# Int_Termostat.net
KiCad netlist of a schematic drawn in EAGLE
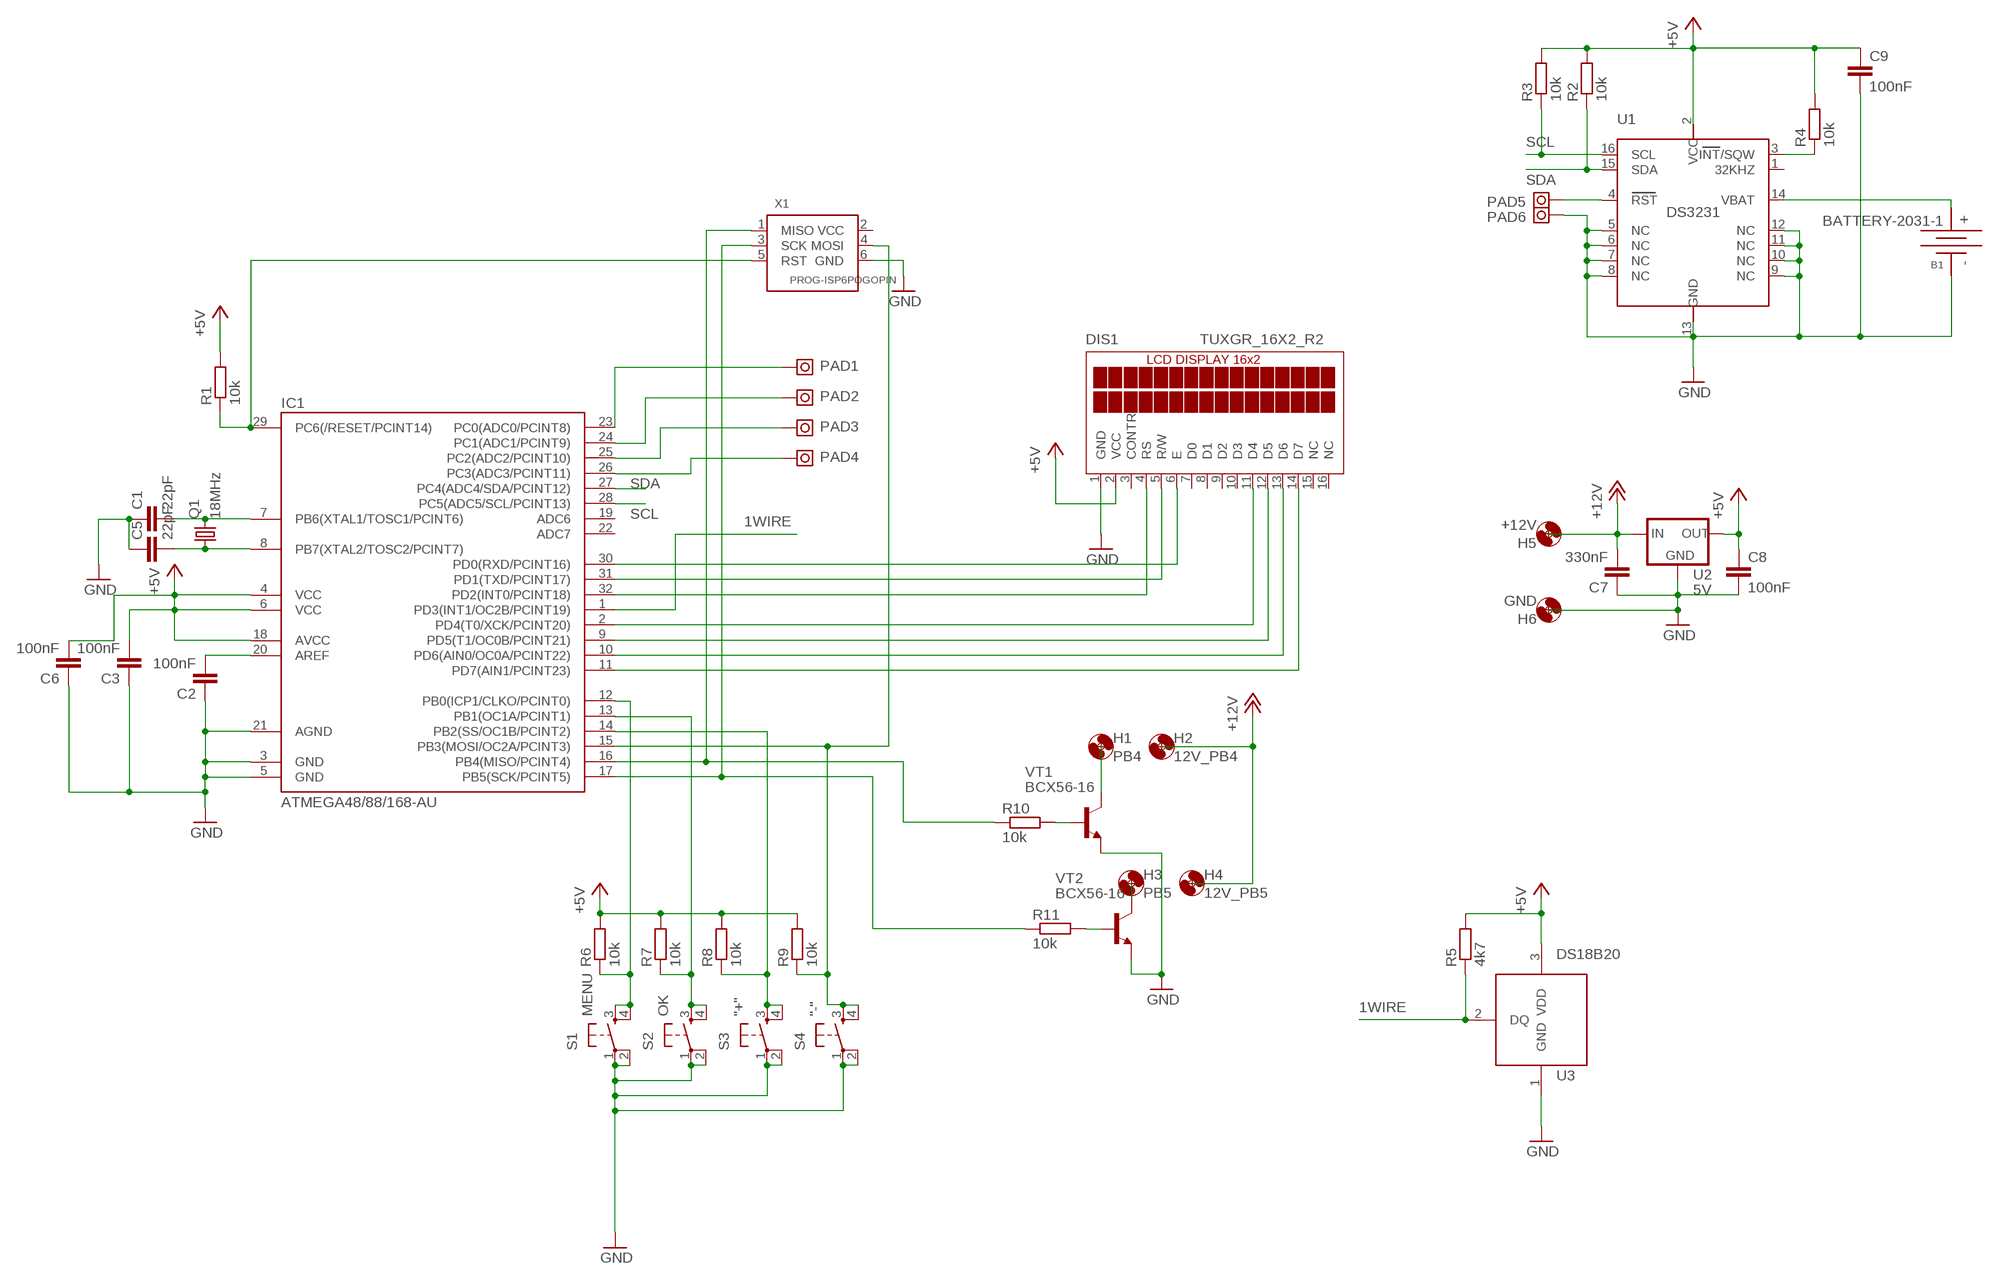
[diagram p0: schematic, sheet 1]

(export (version "E")
  (design (tool "Eeschema 10.0.6"))
  (components
    (comp (ref "B1")
      (value "BATTERY-2031-1")
      (footprint "eagle-import:BTH2032-1")
      (libsource (lib "eagle-import") (part "BATTERY-2031-1"))
    )
    (comp (ref "C1")
      (value "22pF")
      (footprint "eagle-import:C0805")
      (libsource (lib "eagle-import") (part "C-EUC0805"))
    )
    (comp (ref "C2")
      (value "100nF")
      (footprint "eagle-import:C0805")
      (libsource (lib "eagle-import") (part "C-EUC0805"))
    )
    (comp (ref "C3")
      (value "100nF")
      (footprint "eagle-import:C0805")
      (libsource (lib "eagle-import") (part "C-EUC0805"))
    )
    (comp (ref "C5")
      (value "22pF")
      (footprint "eagle-import:C0805")
      (libsource (lib "eagle-import") (part "C-EUC0805"))
    )
    (comp (ref "C6")
      (value "100nF")
      (footprint "eagle-import:C0805")
      (libsource (lib "eagle-import") (part "C-EUC0805"))
    )
    (comp (ref "C7")
      (value "330nF")
      (footprint "eagle-import:C0805")
      (libsource (lib "eagle-import") (part "C-EUC0805"))
    )
    (comp (ref "C8")
      (value "100nF")
      (footprint "eagle-import:C0805")
      (libsource (lib "eagle-import") (part "C-EUC0805"))
    )
    (comp (ref "C9")
      (value "100nF")
      (footprint "eagle-import:C0805")
      (libsource (lib "eagle-import") (part "C-EUC0805"))
    )
    (comp (ref "DIS1")
      (value "TUXGR_16X2_R2")
      (footprint "eagle-import:TUXGR_16X2_R2")
      (libsource (lib "eagle-import") (part "TUXGR_16X2_R2"))
    )
    (comp (ref "H1")
      (value "PB4")
      (footprint "eagle-import:3,0")
      (libsource (lib "eagle-import") (part "MOUNT-HOLE3.0"))
    )
    (comp (ref "H2")
      (value "12V_PB4")
      (footprint "eagle-import:3,0")
      (libsource (lib "eagle-import") (part "MOUNT-HOLE3.0"))
    )
    (comp (ref "H3")
      (value "PB5")
      (footprint "eagle-import:3,0")
      (libsource (lib "eagle-import") (part "MOUNT-HOLE3.0"))
    )
    (comp (ref "H4")
      (value "12V_PB5")
      (footprint "eagle-import:3,0")
      (libsource (lib "eagle-import") (part "MOUNT-HOLE3.0"))
    )
    (comp (ref "H5")
      (value "+12V")
      (footprint "eagle-import:3,0")
      (libsource (lib "eagle-import") (part "MOUNT-HOLE3.0"))
    )
    (comp (ref "H6")
      (value "GND")
      (footprint "eagle-import:3,0")
      (libsource (lib "eagle-import") (part "MOUNT-HOLE3.0"))
    )
    (comp (ref "IC1")
      (value "ATMEGA48/88/168-AU")
      (footprint "eagle-import:TQFP32-08")
      (libsource (lib "eagle-import") (part "ATMEGA48/88/168-AU"))
    )
    (comp (ref "PAD1")
      (value "PC0")
      (footprint "eagle-import:PAD")
      (libsource (lib "eagle-import") (part "PAD"))
    )
    (comp (ref "PAD2")
      (value "PC1")
      (footprint "eagle-import:PAD")
      (libsource (lib "eagle-import") (part "PAD"))
    )
    (comp (ref "PAD3")
      (value "PC2")
      (footprint "eagle-import:PAD")
      (libsource (lib "eagle-import") (part "PAD"))
    )
    (comp (ref "PAD4")
      (value "PC3")
      (footprint "eagle-import:PAD")
      (libsource (lib "eagle-import") (part "PAD"))
    )
    (comp (ref "PAD5")
      (value "RST")
      (footprint "eagle-import:PAD")
      (libsource (lib "eagle-import") (part "PAD"))
    )
    (comp (ref "PAD6")
      (value "RST")
      (footprint "eagle-import:PAD")
      (libsource (lib "eagle-import") (part "PAD"))
    )
    (comp (ref "Q1")
      (value "18MHz")
      (footprint "eagle-import:HC49_S")
      (libsource (lib "eagle-import") (part "CRYSTALHC49S"))
    )
    (comp (ref "R1")
      (value "10k")
      (footprint "eagle-import:R0603")
      (libsource (lib "eagle-import") (part "R-EU_R0603"))
    )
    (comp (ref "R2")
      (value "10k")
      (footprint "eagle-import:R0603")
      (libsource (lib "eagle-import") (part "R-EU_R0603"))
    )
    (comp (ref "R3")
      (value "10k")
      (footprint "eagle-import:R0603")
      (libsource (lib "eagle-import") (part "R-EU_R0603"))
    )
    (comp (ref "R4")
      (value "10k")
      (footprint "eagle-import:R0603")
      (libsource (lib "eagle-import") (part "R-EU_R0603"))
    )
    (comp (ref "R5")
      (value "4k7")
      (footprint "eagle-import:R0603")
      (libsource (lib "eagle-import") (part "R-EU_R0603"))
    )
    (comp (ref "R6")
      (value "10k")
      (footprint "eagle-import:R0603")
      (libsource (lib "eagle-import") (part "R-EU_R0603"))
    )
    (comp (ref "R7")
      (value "10k")
      (footprint "eagle-import:R0603")
      (libsource (lib "eagle-import") (part "R-EU_R0603"))
    )
    (comp (ref "R8")
      (value "10k")
      (footprint "eagle-import:R0603")
      (libsource (lib "eagle-import") (part "R-EU_R0603"))
    )
    (comp (ref "R9")
      (value "10k")
      (footprint "eagle-import:R0603")
      (libsource (lib "eagle-import") (part "R-EU_R0603"))
    )
    (comp (ref "R10")
      (value "10k")
      (footprint "eagle-import:R0603")
      (libsource (lib "eagle-import") (part "R-EU_R0603"))
    )
    (comp (ref "R11")
      (value "10k")
      (footprint "eagle-import:R0603")
      (libsource (lib "eagle-import") (part "R-EU_R0603"))
    )
    (comp (ref "S1")
      (value "MENU")
      (footprint "eagle-import:DTS-6")
      (libsource (lib "eagle-import") (part "DTS-6"))
    )
    (comp (ref "S2")
      (value "OK")
      (footprint "eagle-import:DTS-6")
      (libsource (lib "eagle-import") (part "DTS-6"))
    )
    (comp (ref "S3")
      (value "\"+\"")
      (footprint "eagle-import:DTS-6")
      (libsource (lib "eagle-import") (part "DTS-6"))
    )
    (comp (ref "S4")
      (value "\"-\"")
      (footprint "eagle-import:DTS-6")
      (libsource (lib "eagle-import") (part "DTS-6"))
    )
    (comp (ref "U1")
      (value "DS3231")
      (footprint "eagle-import:SO16")
      (libsource (lib "eagle-import") (part "DS3231"))
    )
    (comp (ref "U2")
      (value "5V")
      (footprint "eagle-import:TO263")
      (libsource (lib "eagle-import") (part "L78XX/TO263"))
    )
    (comp (ref "U3")
      (value "DS18B20")
      (footprint "eagle-import:TO92")
      (libsource (lib "eagle-import") (part "DS18B20"))
    )
    (comp (ref "VT1")
      (value "BCX56-16")
      (footprint "eagle-import:SOT89-ECB")
      (libsource (lib "eagle-import") (part "BCX56-16"))
    )
    (comp (ref "VT2")
      (value "BCX56-16")
      (footprint "eagle-import:SOT89-ECB")
      (libsource (lib "eagle-import") (part "BCX56-16"))
    )
    (comp (ref "X1")
      (value "PROG-ISP6POGOPIN")
      (footprint "eagle-import:PROG_POGOPIN")
      (libsource (lib "eagle-import") (part "PROG-ISP6POGOPIN"))
    )
  )
  (nets
    (net (code "1") (name "+5V") (class "Default")
      (node (ref "C3") (pin "2") (pinfunction "2_2") (pintype "passive"))
      (node (ref "C6") (pin "2") (pinfunction "2_2") (pintype "passive"))
      (node (ref "C8") (pin "1") (pinfunction "1_1") (pintype "passive"))
      (node (ref "C9") (pin "1") (pinfunction "1_1") (pintype "passive"))
      (node (ref "DIS1") (pin "2") (pinfunction "VCC_2") (pintype "power_in"))
      (node (ref "IC1") (pin "18") (pinfunction "AVCC_18") (pintype "passive"))
      (node (ref "IC1") (pin "4") (pinfunction "VCC_4") (pintype "power_in"))
      (node (ref "IC1") (pin "6") (pinfunction "VCC_6") (pintype "power_in"))
      (node (ref "R1") (pin "2") (pinfunction "2_2") (pintype "passive"))
      (node (ref "R2") (pin "2") (pinfunction "2_2") (pintype "passive"))
      (node (ref "R3") (pin "2") (pinfunction "2_2") (pintype "passive"))
      (node (ref "R4") (pin "2") (pinfunction "2_2") (pintype "passive"))
      (node (ref "R5") (pin "2") (pinfunction "2_2") (pintype "passive"))
      (node (ref "R6") (pin "2") (pinfunction "2_2") (pintype "passive"))
      (node (ref "R7") (pin "2") (pinfunction "2_2") (pintype "passive"))
      (node (ref "R8") (pin "2") (pinfunction "2_2") (pintype "passive"))
      (node (ref "R9") (pin "2") (pinfunction "2_2") (pintype "passive"))
      (node (ref "U1") (pin "2") (pinfunction "VCC_2") (pintype "bidirectional"))
      (node (ref "U2") (pin "2") (pinfunction "OUT_2") (pintype "passive"))
      (node (ref "U3") (pin "3") (pinfunction "VDD_3") (pintype "power_in"))
    )
    (net (code "2") (name "+12V") (class "Default")
      (node (ref "C7") (pin "2") (pinfunction "2_2") (pintype "passive"))
      (node (ref "H2") (pin "P$1") (pinfunction "P$1_P$1") (pintype "bidirectional"))
      (node (ref "H4") (pin "P$1") (pinfunction "P$1_P$1") (pintype "bidirectional"))
      (node (ref "H5") (pin "P$1") (pinfunction "P$1_P$1") (pintype "bidirectional"))
      (node (ref "U2") (pin "1") (pinfunction "IN_1") (pintype "input"))
    )
    (net (code "3") (name "/1WIRE") (class "Default")
      (node (ref "IC1") (pin "1") (pinfunction "PD3(INT1/OC2B/PCINT19)_1") (pintype "bidirectional"))
      (node (ref "R5") (pin "1") (pinfunction "1_1") (pintype "passive"))
      (node (ref "U3") (pin "2") (pinfunction "DQ_2") (pintype "bidirectional"))
    )
    (net (code "4") (name "/SCL") (class "Default")
      (node (ref "IC1") (pin "28") (pinfunction "PC5(ADC5/SCL/PCINT13)_28") (pintype "bidirectional"))
      (node (ref "R3") (pin "1") (pinfunction "1_1") (pintype "passive"))
      (node (ref "U1") (pin "16") (pinfunction "SCL_16") (pintype "bidirectional"))
    )
    (net (code "5") (name "/SDA") (class "Default")
      (node (ref "IC1") (pin "27") (pinfunction "PC4(ADC4/SDA/PCINT12)_27") (pintype "bidirectional"))
      (node (ref "R2") (pin "1") (pinfunction "1_1") (pintype "passive"))
      (node (ref "U1") (pin "15") (pinfunction "SDA_15") (pintype "bidirectional"))
    )
    (net (code "6") (name "GND") (class "Default")
      (node (ref "B1") (pin "-") (pinfunction "-_-") (pintype "power_in"))
      (node (ref "C1") (pin "1") (pinfunction "1_1") (pintype "passive"))
      (node (ref "C2") (pin "1") (pinfunction "1_1") (pintype "passive"))
      (node (ref "C3") (pin "1") (pinfunction "1_1") (pintype "passive"))
      (node (ref "C5") (pin "1") (pinfunction "1_1") (pintype "passive"))
      (node (ref "C6") (pin "1") (pinfunction "1_1") (pintype "passive"))
      (node (ref "C7") (pin "1") (pinfunction "1_1") (pintype "passive"))
      (node (ref "C8") (pin "2") (pinfunction "2_2") (pintype "passive"))
      (node (ref "C9") (pin "2") (pinfunction "2_2") (pintype "passive"))
      (node (ref "DIS1") (pin "1") (pinfunction "GND_1") (pintype "power_in"))
      (node (ref "H6") (pin "P$1") (pinfunction "P$1_P$1") (pintype "bidirectional"))
      (node (ref "IC1") (pin "21") (pinfunction "AGND_21") (pintype "power_in"))
      (node (ref "IC1") (pin "3") (pinfunction "GND_3") (pintype "power_in"))
      (node (ref "IC1") (pin "5") (pinfunction "GND_5") (pintype "power_in"))
      (node (ref "PAD6") (pin "P$1") (pinfunction "PAD_P$1") (pintype "bidirectional"))
      (node (ref "S1") (pin "1") (pinfunction "1_1") (pintype "passive"))
      (node (ref "S1") (pin "2") (pinfunction "2_2") (pintype "passive"))
      (node (ref "S2") (pin "1") (pinfunction "1_1") (pintype "passive"))
      (node (ref "S2") (pin "2") (pinfunction "2_2") (pintype "passive"))
      (node (ref "S3") (pin "1") (pinfunction "1_1") (pintype "passive"))
      (node (ref "S3") (pin "2") (pinfunction "2_2") (pintype "passive"))
      (node (ref "S4") (pin "1") (pinfunction "1_1") (pintype "passive"))
      (node (ref "S4") (pin "2") (pinfunction "2_2") (pintype "passive"))
      (node (ref "U1") (pin "10") (pinfunction "NC_10") (pintype "bidirectional"))
      (node (ref "U1") (pin "11") (pinfunction "NC_11") (pintype "bidirectional"))
      (node (ref "U1") (pin "12") (pinfunction "NC_12") (pintype "bidirectional"))
      (node (ref "U1") (pin "13") (pinfunction "GND_13") (pintype "bidirectional"))
      (node (ref "U1") (pin "5") (pinfunction "NC_5") (pintype "bidirectional"))
      (node (ref "U1") (pin "6") (pinfunction "NC_6") (pintype "bidirectional"))
      (node (ref "U1") (pin "7") (pinfunction "NC_7") (pintype "bidirectional"))
      (node (ref "U1") (pin "8") (pinfunction "NC_8") (pintype "bidirectional"))
      (node (ref "U1") (pin "9") (pinfunction "NC_9") (pintype "bidirectional"))
      (node (ref "U2") (pin "3") (pinfunction "GND_3") (pintype "input"))
      (node (ref "U3") (pin "1") (pinfunction "GND_1") (pintype "power_in"))
      (node (ref "VT1") (pin "E") (pinfunction "E_E") (pintype "passive"))
      (node (ref "VT2") (pin "E") (pinfunction "E_E") (pintype "passive"))
      (node (ref "X1") (pin "6") (pinfunction "GND_6") (pintype "bidirectional"))
    )
    (net (code "7") (name "Net-(DIS1-D4)") (class "Default")
      (node (ref "DIS1") (pin "11") (pinfunction "D4_11") (pintype "input"))
      (node (ref "IC1") (pin "2") (pinfunction "PD4(T0/XCK/PCINT20)_2") (pintype "bidirectional"))
    )
    (net (code "8") (name "Net-(DIS1-D5)") (class "Default")
      (node (ref "DIS1") (pin "12") (pinfunction "D5_12") (pintype "input"))
      (node (ref "IC1") (pin "9") (pinfunction "PD5(T1/OC0B/PCINT21)_9") (pintype "bidirectional"))
    )
    (net (code "9") (name "Net-(DIS1-D6)") (class "Default")
      (node (ref "DIS1") (pin "13") (pinfunction "D6_13") (pintype "input"))
      (node (ref "IC1") (pin "10") (pinfunction "PD6(AIN0/OC0A/PCINT22)_10") (pintype "bidirectional"))
    )
    (net (code "10") (name "Net-(DIS1-D7)") (class "Default")
      (node (ref "DIS1") (pin "14") (pinfunction "D7_14") (pintype "input"))
      (node (ref "IC1") (pin "11") (pinfunction "PD7(AIN1/PCINT23)_11") (pintype "bidirectional"))
    )
    (net (code "11") (name "Net-(DIS1-E)") (class "Default")
      (node (ref "DIS1") (pin "6") (pinfunction "E_6") (pintype "input"))
      (node (ref "IC1") (pin "30") (pinfunction "PD0(RXD/PCINT16)_30") (pintype "bidirectional"))
    )
    (net (code "12") (name "Net-(DIS1-RS)") (class "Default")
      (node (ref "DIS1") (pin "4") (pinfunction "RS_4") (pintype "input"))
      (node (ref "IC1") (pin "32") (pinfunction "PD2(INT0/PCINT18)_32") (pintype "bidirectional"))
    )
    (net (code "13") (name "Net-(DIS1-R{slash}W)") (class "Default")
      (node (ref "DIS1") (pin "5") (pinfunction "R/W_5") (pintype "input"))
      (node (ref "IC1") (pin "31") (pinfunction "PD1(TXD/PCINT17)_31") (pintype "bidirectional"))
    )
    (net (code "14") (name "Net-(H1-PadP$1)") (class "Default")
      (node (ref "H1") (pin "P$1") (pinfunction "P$1_P$1") (pintype "bidirectional"))
      (node (ref "VT1") (pin "C") (pinfunction "C_C") (pintype "passive"))
      (node (ref "VT1") (pin "C@1") (pinfunction "C_C@1") (pintype "passive"))
    )
    (net (code "15") (name "Net-(H3-PadP$1)") (class "Default")
      (node (ref "H3") (pin "P$1") (pinfunction "P$1_P$1") (pintype "bidirectional"))
      (node (ref "VT2") (pin "C") (pinfunction "C_C") (pintype "passive"))
      (node (ref "VT2") (pin "C@1") (pinfunction "C_C@1") (pintype "passive"))
    )
    (net (code "16") (name "Net-(IC1-AREF)") (class "Default")
      (node (ref "C2") (pin "2") (pinfunction "2_2") (pintype "passive"))
      (node (ref "IC1") (pin "20") (pinfunction "AREF_20") (pintype "passive"))
    )
    (net (code "17") (name "Net-(IC1-PB0(ICP1{slash}CLKO{slash}PCINT0))") (class "Default")
      (node (ref "IC1") (pin "12") (pinfunction "PB0(ICP1/CLKO/PCINT0)_12") (pintype "bidirectional"))
      (node (ref "R6") (pin "1") (pinfunction "1_1") (pintype "passive"))
      (node (ref "S1") (pin "3") (pinfunction "3_3") (pintype "passive"))
      (node (ref "S1") (pin "4") (pinfunction "4_4") (pintype "passive"))
    )
    (net (code "18") (name "Net-(IC1-PB1(OC1A{slash}PCINT1))") (class "Default")
      (node (ref "IC1") (pin "13") (pinfunction "PB1(OC1A/PCINT1)_13") (pintype "bidirectional"))
      (node (ref "R7") (pin "1") (pinfunction "1_1") (pintype "passive"))
      (node (ref "S2") (pin "3") (pinfunction "3_3") (pintype "passive"))
      (node (ref "S2") (pin "4") (pinfunction "4_4") (pintype "passive"))
    )
    (net (code "19") (name "Net-(IC1-PB2(SS{slash}OC1B{slash}PCINT2))") (class "Default")
      (node (ref "IC1") (pin "14") (pinfunction "PB2(SS/OC1B/PCINT2)_14") (pintype "bidirectional"))
      (node (ref "R8") (pin "1") (pinfunction "1_1") (pintype "passive"))
      (node (ref "S3") (pin "3") (pinfunction "3_3") (pintype "passive"))
      (node (ref "S3") (pin "4") (pinfunction "4_4") (pintype "passive"))
    )
    (net (code "20") (name "Net-(IC1-PB3(MOSI{slash}OC2A{slash}PCINT3))") (class "Default")
      (node (ref "IC1") (pin "15") (pinfunction "PB3(MOSI/OC2A/PCINT3)_15") (pintype "bidirectional"))
      (node (ref "R9") (pin "1") (pinfunction "1_1") (pintype "passive"))
      (node (ref "S4") (pin "3") (pinfunction "3_3") (pintype "passive"))
      (node (ref "S4") (pin "4") (pinfunction "4_4") (pintype "passive"))
      (node (ref "X1") (pin "4") (pinfunction "MOSI_4") (pintype "bidirectional"))
    )
    (net (code "21") (name "Net-(IC1-PB4(MISO{slash}PCINT4))") (class "Default")
      (node (ref "IC1") (pin "16") (pinfunction "PB4(MISO/PCINT4)_16") (pintype "bidirectional"))
      (node (ref "R10") (pin "1") (pinfunction "1_1") (pintype "passive"))
      (node (ref "X1") (pin "1") (pinfunction "MISO_1") (pintype "bidirectional"))
    )
    (net (code "22") (name "Net-(IC1-PB5(SCK{slash}PCINT5))") (class "Default")
      (node (ref "IC1") (pin "17") (pinfunction "PB5(SCK/PCINT5)_17") (pintype "bidirectional"))
      (node (ref "R11") (pin "1") (pinfunction "1_1") (pintype "passive"))
      (node (ref "X1") (pin "3") (pinfunction "SCK_3") (pintype "bidirectional"))
    )
    (net (code "23") (name "Net-(IC1-PB6(XTAL1{slash}TOSC1{slash}PCINT6))") (class "Default")
      (node (ref "C1") (pin "2") (pinfunction "2_2") (pintype "passive"))
      (node (ref "IC1") (pin "7") (pinfunction "PB6(XTAL1/TOSC1/PCINT6)_7") (pintype "bidirectional"))
      (node (ref "Q1") (pin "2") (pinfunction "2_2") (pintype "passive"))
    )
    (net (code "24") (name "Net-(IC1-PB7(XTAL2{slash}TOSC2{slash}PCINT7))") (class "Default")
      (node (ref "C5") (pin "2") (pinfunction "2_2") (pintype "passive"))
      (node (ref "IC1") (pin "8") (pinfunction "PB7(XTAL2/TOSC2/PCINT7)_8") (pintype "bidirectional"))
      (node (ref "Q1") (pin "1") (pinfunction "1_1") (pintype "passive"))
    )
    (net (code "25") (name "Net-(IC1-PC0(ADC0{slash}PCINT8))") (class "Default")
      (node (ref "IC1") (pin "23") (pinfunction "PC0(ADC0/PCINT8)_23") (pintype "bidirectional"))
      (node (ref "PAD1") (pin "P$1") (pinfunction "PAD_P$1") (pintype "bidirectional"))
    )
    (net (code "26") (name "Net-(IC1-PC1(ADC1{slash}PCINT9))") (class "Default")
      (node (ref "IC1") (pin "24") (pinfunction "PC1(ADC1/PCINT9)_24") (pintype "bidirectional"))
      (node (ref "PAD2") (pin "P$1") (pinfunction "PAD_P$1") (pintype "bidirectional"))
    )
    (net (code "27") (name "Net-(IC1-PC2(ADC2{slash}PCINT10))") (class "Default")
      (node (ref "IC1") (pin "25") (pinfunction "PC2(ADC2/PCINT10)_25") (pintype "bidirectional"))
      (node (ref "PAD3") (pin "P$1") (pinfunction "PAD_P$1") (pintype "bidirectional"))
    )
    (net (code "28") (name "Net-(IC1-PC3(ADC3{slash}PCINT11))") (class "Default")
      (node (ref "IC1") (pin "26") (pinfunction "PC3(ADC3/PCINT11)_26") (pintype "bidirectional"))
      (node (ref "PAD4") (pin "P$1") (pinfunction "PAD_P$1") (pintype "bidirectional"))
    )
    (net (code "29") (name "Net-(IC1-PC6({slash}RESET{slash}PCINT14))") (class "Default")
      (node (ref "IC1") (pin "29") (pinfunction "PC6(/RESET/PCINT14)_29") (pintype "bidirectional"))
      (node (ref "R1") (pin "1") (pinfunction "1_1") (pintype "passive"))
      (node (ref "X1") (pin "5") (pinfunction "RST_5") (pintype "bidirectional"))
    )
    (net (code "30") (name "Net-(PAD5-PAD)") (class "Default")
      (node (ref "PAD5") (pin "P$1") (pinfunction "PAD_P$1") (pintype "bidirectional"))
      (node (ref "U1") (pin "4") (pinfunction "RST_4") (pintype "bidirectional"))
    )
    (net (code "31") (name "Net-(R10-Pad2)") (class "Default")
      (node (ref "R10") (pin "2") (pinfunction "2_2") (pintype "passive"))
      (node (ref "VT1") (pin "B") (pinfunction "B_B") (pintype "passive"))
    )
    (net (code "32") (name "Net-(R11-Pad2)") (class "Default")
      (node (ref "R11") (pin "2") (pinfunction "2_2") (pintype "passive"))
      (node (ref "VT2") (pin "B") (pinfunction "B_B") (pintype "passive"))
    )
    (net (code "33") (name "Net-(U1-INT{slash}SQW)") (class "Default")
      (node (ref "R4") (pin "1") (pinfunction "1_1") (pintype "passive"))
      (node (ref "U1") (pin "3") (pinfunction "INT/SQW_3") (pintype "bidirectional"))
    )
    (net (code "34") (name "Net-(U1-VBAT)") (class "Default")
      (node (ref "B1") (pin "+") (pinfunction "+_+") (pintype "power_in"))
      (node (ref "U1") (pin "14") (pinfunction "VBAT_14") (pintype "bidirectional"))
    )
    (net (code "35") (name "unconnected-(DIS1-CONTR-Pad3)") (class "Default")
      (node (ref "DIS1") (pin "3") (pinfunction "CONTR_3") (pintype "input"))
    )
    (net (code "36") (name "unconnected-(DIS1-D0-Pad7)") (class "Default")
      (node (ref "DIS1") (pin "7") (pinfunction "D0_7") (pintype "input"))
    )
    (net (code "37") (name "unconnected-(DIS1-D1-Pad8)") (class "Default")
      (node (ref "DIS1") (pin "8") (pinfunction "D1_8") (pintype "input"))
    )
    (net (code "38") (name "unconnected-(DIS1-D2-Pad9)") (class "Default")
      (node (ref "DIS1") (pin "9") (pinfunction "D2_9") (pintype "input"))
    )
    (net (code "39") (name "unconnected-(DIS1-D3-Pad10)") (class "Default")
      (node (ref "DIS1") (pin "10") (pinfunction "D3_10") (pintype "input"))
    )
    (net (code "40") (name "unconnected-(DIS1-NC-Pad15)") (class "Default")
      (node (ref "DIS1") (pin "15") (pinfunction "NC_15") (pintype "no_connect"))
    )
    (net (code "41") (name "unconnected-(DIS1-NC-Pad16)") (class "Default")
      (node (ref "DIS1") (pin "16") (pinfunction "NC_16") (pintype "no_connect"))
    )
    (net (code "42") (name "unconnected-(IC1-ADC6-Pad19)") (class "Default")
      (node (ref "IC1") (pin "19") (pinfunction "ADC6_19") (pintype "passive"))
    )
    (net (code "43") (name "unconnected-(IC1-ADC7-Pad22)") (class "Default")
      (node (ref "IC1") (pin "22") (pinfunction "ADC7_22") (pintype "passive"))
    )
    (net (code "44") (name "unconnected-(U1-32KHZ-Pad1)") (class "Default")
      (node (ref "U1") (pin "1") (pinfunction "32KHZ_1") (pintype "bidirectional"))
    )
    (net (code "45") (name "unconnected-(X1-VCC-Pad2)") (class "Default")
      (node (ref "X1") (pin "2") (pinfunction "VCC_2") (pintype "bidirectional"))
    )
  )
)
